# 30x70-motor-controller-0_3.net
KiCad netlist of a schematic drawn in EAGLE
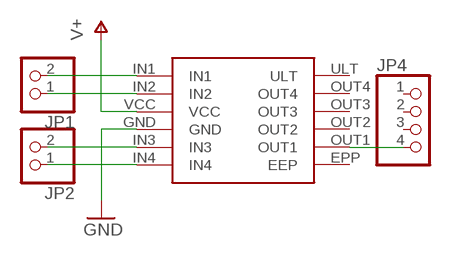
[diagram p0: schematic, sheet 1]
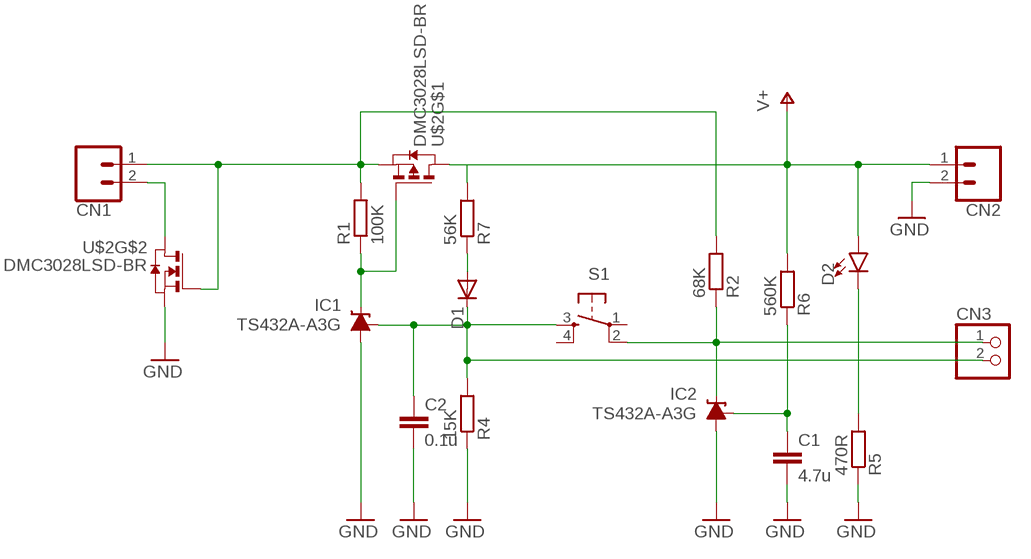
[diagram p1: schematic, sheet 2]

(export (version "E")
  (design (tool "Eeschema 10.0.6"))
  (components
    (comp (ref "C1")
      (value "4.7u")
      (footprint "eagle-import:C025-025X050")
      (libsource (lib "eagle-import") (part "C-EU025-025X050"))
    )
    (comp (ref "C2")
      (value "0.1u")
      (footprint "eagle-import:C025-024X044")
      (libsource (lib "eagle-import") (part "C-EU025-024X044"))
    )
    (comp (ref "CN1")
      (value "CONN_02-JST-XTH")
      (footprint "eagle-import:JST-2-XTH")
      (libsource (lib "eagle-import") (part "CONN_02-JST-XTH"))
    )
    (comp (ref "CN2")
      (value "CONN_02-JST-XTH")
      (footprint "eagle-import:JST-2-XTH")
      (libsource (lib "eagle-import") (part "CONN_02-JST-XTH"))
    )
    (comp (ref "CN3")
      (value "PINHD-1X2/90")
      (footprint "eagle-import:1X02_90")
      (libsource (lib "eagle-import") (part "PINHD-1X2/90"))
    )
    (comp (ref "D1")
      (value "DIODE-D-2.5")
      (footprint "eagle-import:D-2.5")
      (libsource (lib "eagle-import") (part "DIODE-D-2.5"))
    )
    (comp (ref "D2")
      (value "LED-3MM-NO_SILK")
      (footprint "eagle-import:LED_3MM-NS")
      (libsource (lib "eagle-import") (part "LED-3MM-NO_SILK"))
    )
    (comp (ref "IC1")
      (value "TS432A-A3G")
      (footprint "eagle-import:TO92-LINE")
      (libsource (lib "eagle-import") (part "TS432A-A3G"))
    )
    (comp (ref "IC2")
      (value "TS432A-A3G")
      (footprint "eagle-import:TO92-LINE")
      (libsource (lib "eagle-import") (part "TS432A-A3G"))
    )
    (comp (ref "R1")
      (value "100K")
      (footprint "eagle-import:0204V")
      (libsource (lib "eagle-import") (part "R-EU_0204/2V"))
    )
    (comp (ref "R2")
      (value "68K")
      (footprint "eagle-import:0207_15")
      (libsource (lib "eagle-import") (part "R-EU_0207/15"))
    )
    (comp (ref "R4")
      (value "15K")
      (footprint "eagle-import:0204V")
      (libsource (lib "eagle-import") (part "R-EU_0204/2V"))
    )
    (comp (ref "R5")
      (value "470R")
      (footprint "eagle-import:0204V")
      (libsource (lib "eagle-import") (part "R-EU_0204/2V"))
    )
    (comp (ref "R6")
      (value "560K")
      (footprint "eagle-import:0204V")
      (libsource (lib "eagle-import") (part "R-EU_0204/2V"))
    )
    (comp (ref "R7")
      (value "56K")
      (footprint "eagle-import:0204_7")
      (libsource (lib "eagle-import") (part "R-EU_0204/7"))
    )
    (comp (ref "S1")
      (value "PROTO-MICRO-SWITCH")
      (footprint "eagle-import:B3F-10XX-PROTO")
      (libsource (lib "eagle-import") (part "PROTO-MICRO-SWITCH"))
    )
    (comp (ref "U$2")
      (value "DMC3028LSD-BR")
      (footprint "eagle-import:DIL8-BREAKOUT")
      (libsource (lib "eagle-import") (part "DMC3028LSD-BR"))
    )
    (comp (ref "JP1")
      (value "PINHD-1X2/90")
      (footprint "eagle-import:1X02_90")
      (libsource (lib "eagle-import") (part "PINHD-1X2/90"))
    )
    (comp (ref "JP2")
      (value "PINHD-1X2/90")
      (footprint "eagle-import:1X02_90")
      (libsource (lib "eagle-import") (part "PINHD-1X2/90"))
    )
    (comp (ref "JP4")
      (value "PINHD-1X4/90")
      (footprint "eagle-import:1X04_90")
      (libsource (lib "eagle-import") (part "PINHD-1X4/90"))
    )
    (comp (ref "U$1")
      (value "DRV8833-MODULE")
      (footprint "eagle-import:DRV8833-BRKOUT")
      (libsource (lib "eagle-import") (part "DRV8833-MODULE"))
    )
  )
  (nets
    (net (code "1") (name "GND") (class "Default")
      (node (ref "C1") (pin "2") (pinfunction "2_2") (pintype "passive"))
      (node (ref "C2") (pin "2") (pinfunction "2_2") (pintype "passive"))
      (node (ref "CN2") (pin "2") (pinfunction "2_2") (pintype "passive"))
      (node (ref "IC1") (pin "2") (pinfunction "A_2") (pintype "passive"))
      (node (ref "IC2") (pin "2") (pinfunction "A_2") (pintype "passive"))
      (node (ref "R4") (pin "1") (pinfunction "1_1") (pintype "passive"))
      (node (ref "R5") (pin "1") (pinfunction "1_1") (pintype "passive"))
      (node (ref "U$1") (pin "GND") (pinfunction "GND_GND") (pintype "bidirectional"))
      (node (ref "U$2") (pin "1") (pinfunction "S_1") (pintype "passive"))
    )
    (net (code "2") (name "Net-(CN1-Pad2)") (class "Default")
      (node (ref "CN1") (pin "2") (pinfunction "2_2") (pintype "passive"))
      (node (ref "U$2") (pin "7") (pinfunction "D_7") (pintype "passive"))
      (node (ref "U$2") (pin "8") (pinfunction "D_8") (pintype "passive"))
    )
    (net (code "3") (name "Net-(D1-PadA)") (class "Default")
      (node (ref "D1") (pin "A") (pinfunction "A_A") (pintype "passive"))
      (node (ref "R7") (pin "1") (pinfunction "1_1") (pintype "passive"))
    )
    (net (code "4") (name "Net-(D2-C)") (class "Default")
      (node (ref "D2") (pin "K") (pinfunction "C_K") (pintype "passive"))
      (node (ref "R5") (pin "2") (pinfunction "2_2") (pintype "passive"))
    )
    (net (code "5") (name "Net-(IC1-C)") (class "Default")
      (node (ref "IC1") (pin "1") (pinfunction "C_1") (pintype "passive"))
      (node (ref "R1") (pin "1") (pinfunction "1_1") (pintype "passive"))
      (node (ref "U$2") (pin "4") (pinfunction "G_4") (pintype "passive"))
    )
    (net (code "6") (name "Net-(IC1-FB)") (class "Default")
      (node (ref "C2") (pin "1") (pinfunction "1_1") (pintype "passive"))
      (node (ref "CN3") (pin "2") (pinfunction "2_2") (pintype "passive"))
      (node (ref "D1") (pin "C") (pinfunction "C_C") (pintype "passive"))
      (node (ref "IC1") (pin "3") (pinfunction "FB_3") (pintype "passive"))
      (node (ref "R4") (pin "2") (pinfunction "2_2") (pintype "passive"))
      (node (ref "S1") (pin "3") (pinfunction "S_3") (pintype "passive"))
    )
    (net (code "7") (name "Net-(IC2-C)") (class "Default")
      (node (ref "CN3") (pin "1") (pinfunction "1_1") (pintype "passive"))
      (node (ref "IC2") (pin "1") (pinfunction "C_1") (pintype "passive"))
      (node (ref "R2") (pin "1") (pinfunction "1_1") (pintype "passive"))
      (node (ref "S1") (pin "2") (pinfunction "P1_2") (pintype "passive"))
    )
    (net (code "8") (name "Net-(IC2-FB)") (class "Default")
      (node (ref "C1") (pin "1") (pinfunction "1_1") (pintype "passive"))
      (node (ref "IC2") (pin "3") (pinfunction "FB_3") (pintype "passive"))
      (node (ref "R6") (pin "1") (pinfunction "1_1") (pintype "passive"))
    )
    (net (code "9") (name "Net-(JP1-Pad1)") (class "Default")
      (node (ref "JP1") (pin "1") (pinfunction "1_1") (pintype "passive"))
      (node (ref "U$1") (pin "IN2") (pinfunction "IN2_IN2") (pintype "bidirectional"))
    )
    (net (code "10") (name "Net-(JP1-Pad2)") (class "Default")
      (node (ref "JP1") (pin "2") (pinfunction "2_2") (pintype "passive"))
      (node (ref "U$1") (pin "IN1") (pinfunction "IN1_IN1") (pintype "bidirectional"))
    )
    (net (code "11") (name "Net-(JP2-Pad1)") (class "Default")
      (node (ref "JP2") (pin "1") (pinfunction "1_1") (pintype "passive"))
      (node (ref "U$1") (pin "IN4") (pinfunction "IN4_IN4") (pintype "bidirectional"))
    )
    (net (code "12") (name "Net-(JP2-Pad2)") (class "Default")
      (node (ref "JP2") (pin "2") (pinfunction "2_2") (pintype "passive"))
      (node (ref "U$1") (pin "IN3") (pinfunction "IN3_IN3") (pintype "bidirectional"))
    )
    (net (code "13") (name "Net-(JP4-Pad4)") (class "Default")
      (node (ref "JP4") (pin "4") (pinfunction "4_4") (pintype "passive"))
      (node (ref "U$1") (pin "OUT1") (pinfunction "OUT1_OUT1") (pintype "bidirectional"))
    )
    (net (code "14") (name "Net-(U$2A-S)") (class "Default")
      (node (ref "CN1") (pin "1") (pinfunction "1_1") (pintype "passive"))
      (node (ref "R1") (pin "2") (pinfunction "2_2") (pintype "passive"))
      (node (ref "R2") (pin "2") (pinfunction "2_2") (pintype "passive"))
      (node (ref "U$2") (pin "2") (pinfunction "G_2") (pintype "passive"))
      (node (ref "U$2") (pin "3") (pinfunction "S_3") (pintype "passive"))
    )
    (net (code "15") (name "V+") (class "Default")
      (node (ref "CN2") (pin "1") (pinfunction "1_1") (pintype "passive"))
      (node (ref "D2") (pin "A") (pinfunction "A_A") (pintype "passive"))
      (node (ref "R6") (pin "2") (pinfunction "2_2") (pintype "passive"))
      (node (ref "R7") (pin "2") (pinfunction "2_2") (pintype "passive"))
      (node (ref "U$1") (pin "VCC") (pinfunction "VCC_VCC") (pintype "bidirectional"))
      (node (ref "U$2") (pin "5") (pinfunction "D_5") (pintype "passive"))
      (node (ref "U$2") (pin "6") (pinfunction "D_6") (pintype "passive"))
    )
    (net (code "16") (name "unconnected-(JP4-Pad1)") (class "Default")
      (node (ref "JP4") (pin "1") (pinfunction "1_1") (pintype "passive"))
    )
    (net (code "17") (name "unconnected-(JP4-Pad2)") (class "Default")
      (node (ref "JP4") (pin "2") (pinfunction "2_2") (pintype "passive"))
    )
    (net (code "18") (name "unconnected-(JP4-Pad3)") (class "Default")
      (node (ref "JP4") (pin "3") (pinfunction "3_3") (pintype "passive"))
    )
    (net (code "19") (name "unconnected-(S1-P-Pad1)") (class "Default")
      (node (ref "S1") (pin "1") (pinfunction "P_1") (pintype "passive"))
    )
    (net (code "20") (name "unconnected-(S1-S1-Pad4)") (class "Default")
      (node (ref "S1") (pin "4") (pinfunction "S1_4") (pintype "passive"))
    )
    (net (code "21") (name "unconnected-(U$1-EEP-PadEPP)") (class "Default")
      (node (ref "U$1") (pin "EPP") (pinfunction "EEP_EPP") (pintype "bidirectional"))
    )
    (net (code "22") (name "unconnected-(U$1-PadOUT2)") (class "Default")
      (node (ref "U$1") (pin "OUT2") (pinfunction "OUT2_OUT2") (pintype "bidirectional"))
    )
    (net (code "23") (name "unconnected-(U$1-PadOUT3)") (class "Default")
      (node (ref "U$1") (pin "OUT3") (pinfunction "OUT3_OUT3") (pintype "bidirectional"))
    )
    (net (code "24") (name "unconnected-(U$1-PadOUT4)") (class "Default")
      (node (ref "U$1") (pin "OUT4") (pinfunction "OUT4_OUT4") (pintype "bidirectional"))
    )
    (net (code "25") (name "unconnected-(U$1-PadULT)") (class "Default")
      (node (ref "U$1") (pin "ULT") (pinfunction "ULT_ULT") (pintype "bidirectional"))
    )
  )
)
